# NeoGeo-JAMMA-Supergun_OD.net
KiCad netlist of a schematic drawn in EAGLE
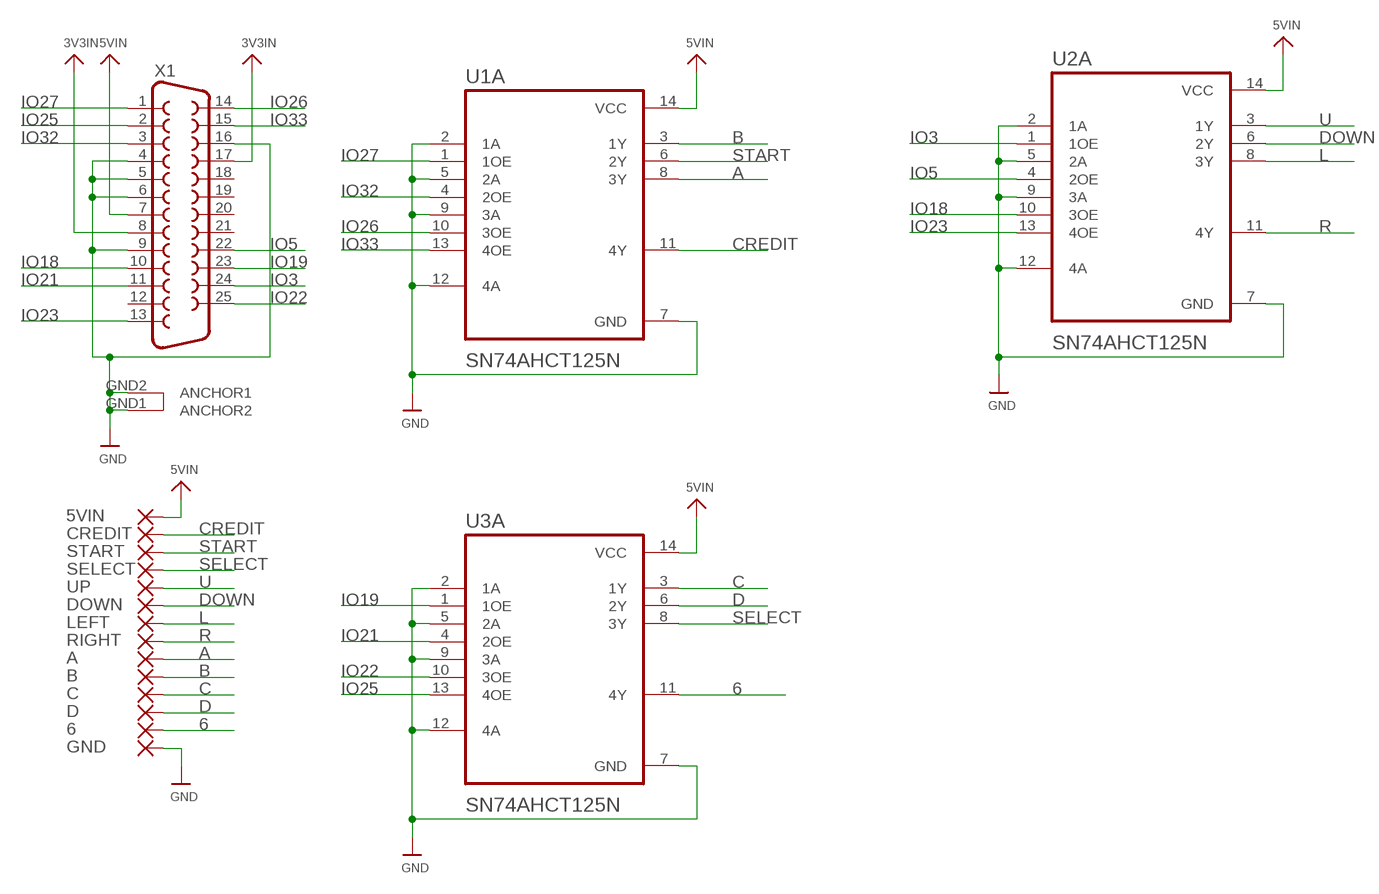
[diagram p0: schematic, sheet 1]

(export (version "E")
  (design (tool "Eeschema 10.0.6"))
  (components
    (comp (ref "5VIN")
      (value "SMD5")
      (footprint "eagle-import:SMD2,54-5,08")
      (libsource (lib "eagle-import") (part "SMD5"))
    )
    (comp (ref "6")
      (value "SMD5")
      (footprint "eagle-import:SMD2,54-5,08")
      (libsource (lib "eagle-import") (part "SMD5"))
    )
    (comp (ref "A")
      (value "SMD5")
      (footprint "eagle-import:SMD2,54-5,08")
      (libsource (lib "eagle-import") (part "SMD5"))
    )
    (comp (ref "B")
      (value "SMD5")
      (footprint "eagle-import:SMD2,54-5,08")
      (libsource (lib "eagle-import") (part "SMD5"))
    )
    (comp (ref "C")
      (value "SMD5")
      (footprint "eagle-import:SMD2,54-5,08")
      (libsource (lib "eagle-import") (part "SMD5"))
    )
    (comp (ref "CREDIT")
      (value "SMD5")
      (footprint "eagle-import:SMD2,54-5,08")
      (libsource (lib "eagle-import") (part "SMD5"))
    )
    (comp (ref "D")
      (value "SMD5")
      (footprint "eagle-import:SMD2,54-5,08")
      (libsource (lib "eagle-import") (part "SMD5"))
    )
    (comp (ref "DOWN")
      (value "SMD5")
      (footprint "eagle-import:SMD2,54-5,08")
      (libsource (lib "eagle-import") (part "SMD5"))
    )
    (comp (ref "GND")
      (value "SMD5")
      (footprint "eagle-import:SMD2,54-5,08")
      (libsource (lib "eagle-import") (part "SMD5"))
    )
    (comp (ref "LEFT")
      (value "SMD5")
      (footprint "eagle-import:SMD2,54-5,08")
      (libsource (lib "eagle-import") (part "SMD5"))
    )
    (comp (ref "RIGHT")
      (value "SMD5")
      (footprint "eagle-import:SMD2,54-5,08")
      (libsource (lib "eagle-import") (part "SMD5"))
    )
    (comp (ref "SELECT")
      (value "SMD5")
      (footprint "eagle-import:SMD2,54-5,08")
      (libsource (lib "eagle-import") (part "SMD5"))
    )
    (comp (ref "START")
      (value "SMD5")
      (footprint "eagle-import:SMD2,54-5,08")
      (libsource (lib "eagle-import") (part "SMD5"))
    )
    (comp (ref "U1A")
      (value "SN74AHCT125N")
      (footprint "eagle-import:DIP794W45P254L1969H508Q14")
      (fields (field (name "MF") "Texas Instruments"))
      (libsource (lib "eagle-import") (part "SN74AHCT125N"))
    )
    (comp (ref "U2A")
      (value "SN74AHCT125N")
      (footprint "eagle-import:DIP794W45P254L1969H508Q14")
      (fields (field (name "MF") "Texas Instruments"))
      (libsource (lib "eagle-import") (part "SN74AHCT125N"))
    )
    (comp (ref "U3A")
      (value "SN74AHCT125N")
      (footprint "eagle-import:DIP794W45P254L1969H508Q14")
      (fields (field (name "MF") "Texas Instruments"))
      (libsource (lib "eagle-import") (part "SN74AHCT125N"))
    )
    (comp (ref "UP")
      (value "SMD5")
      (footprint "eagle-import:SMD2,54-5,08")
      (libsource (lib "eagle-import") (part "SMD5"))
    )
    (comp (ref "X1")
      (value "DB25_FEMALEHP")
      (footprint "eagle-import:F25HP")
      (libsource (lib "eagle-import") (part "DB25_FEMALEHP"))
    )
  )
  (nets
    (net (code "1") (name "/6") (class "Default")
      (node (ref "6") (pin "1") (pinfunction "P_1") (pintype "passive"))
      (node (ref "U3A") (pin "11") (pinfunction "4Y_11") (pintype "output"))
    )
    (net (code "2") (name "/A") (class "Default")
      (node (ref "A") (pin "1") (pinfunction "P_1") (pintype "passive"))
      (node (ref "U1A") (pin "8") (pinfunction "3Y_8") (pintype "output"))
    )
    (net (code "3") (name "/B") (class "Default")
      (node (ref "B") (pin "1") (pinfunction "P_1") (pintype "passive"))
      (node (ref "U1A") (pin "3") (pinfunction "1Y_3") (pintype "output"))
    )
    (net (code "4") (name "/C") (class "Default")
      (node (ref "C") (pin "1") (pinfunction "P_1") (pintype "passive"))
      (node (ref "U3A") (pin "3") (pinfunction "1Y_3") (pintype "output"))
    )
    (net (code "5") (name "/CREDIT") (class "Default")
      (node (ref "CREDIT") (pin "1") (pinfunction "P_1") (pintype "passive"))
      (node (ref "U1A") (pin "11") (pinfunction "4Y_11") (pintype "output"))
    )
    (net (code "6") (name "/D") (class "Default")
      (node (ref "D") (pin "1") (pinfunction "P_1") (pintype "passive"))
      (node (ref "U3A") (pin "6") (pinfunction "2Y_6") (pintype "output"))
    )
    (net (code "7") (name "/DOWN") (class "Default")
      (node (ref "DOWN") (pin "1") (pinfunction "P_1") (pintype "passive"))
      (node (ref "U2A") (pin "6") (pinfunction "2Y_6") (pintype "output"))
    )
    (net (code "8") (name "/IO3") (class "Default")
      (node (ref "U2A") (pin "1") (pinfunction "1OE_1") (pintype "input"))
      (node (ref "X1") (pin "24") (pinfunction "24_24") (pintype "passive"))
    )
    (net (code "9") (name "/IO5") (class "Default")
      (node (ref "U2A") (pin "4") (pinfunction "2OE_4") (pintype "input"))
      (node (ref "X1") (pin "22") (pinfunction "22_22") (pintype "passive"))
    )
    (net (code "10") (name "/IO18") (class "Default")
      (node (ref "U2A") (pin "10") (pinfunction "3OE_10") (pintype "input"))
      (node (ref "X1") (pin "10") (pinfunction "10_10") (pintype "passive"))
    )
    (net (code "11") (name "/IO19") (class "Default")
      (node (ref "U3A") (pin "1") (pinfunction "1OE_1") (pintype "input"))
      (node (ref "X1") (pin "23") (pinfunction "23_23") (pintype "passive"))
    )
    (net (code "12") (name "/IO21") (class "Default")
      (node (ref "U3A") (pin "4") (pinfunction "2OE_4") (pintype "input"))
      (node (ref "X1") (pin "11") (pinfunction "11_11") (pintype "passive"))
    )
    (net (code "13") (name "/IO22") (class "Default")
      (node (ref "U3A") (pin "10") (pinfunction "3OE_10") (pintype "input"))
      (node (ref "X1") (pin "25") (pinfunction "25_25") (pintype "passive"))
    )
    (net (code "14") (name "/IO23") (class "Default")
      (node (ref "U2A") (pin "13") (pinfunction "4OE_13") (pintype "input"))
      (node (ref "X1") (pin "13") (pinfunction "13_13") (pintype "passive"))
    )
    (net (code "15") (name "/IO25") (class "Default")
      (node (ref "U3A") (pin "13") (pinfunction "4OE_13") (pintype "input"))
      (node (ref "X1") (pin "2") (pinfunction "2_2") (pintype "passive"))
    )
    (net (code "16") (name "/IO26") (class "Default")
      (node (ref "U1A") (pin "10") (pinfunction "3OE_10") (pintype "input"))
      (node (ref "X1") (pin "14") (pinfunction "14_14") (pintype "passive"))
    )
    (net (code "17") (name "/IO27") (class "Default")
      (node (ref "U1A") (pin "1") (pinfunction "1OE_1") (pintype "input"))
      (node (ref "X1") (pin "1") (pinfunction "1_1") (pintype "passive"))
    )
    (net (code "18") (name "/IO32") (class "Default")
      (node (ref "U1A") (pin "4") (pinfunction "2OE_4") (pintype "input"))
      (node (ref "X1") (pin "3") (pinfunction "3_3") (pintype "passive"))
    )
    (net (code "19") (name "/IO33") (class "Default")
      (node (ref "U1A") (pin "13") (pinfunction "4OE_13") (pintype "input"))
      (node (ref "X1") (pin "15") (pinfunction "15_15") (pintype "passive"))
    )
    (net (code "20") (name "/L") (class "Default")
      (node (ref "LEFT") (pin "1") (pinfunction "P_1") (pintype "passive"))
      (node (ref "U2A") (pin "8") (pinfunction "3Y_8") (pintype "output"))
    )
    (net (code "21") (name "/R") (class "Default")
      (node (ref "RIGHT") (pin "1") (pinfunction "P_1") (pintype "passive"))
      (node (ref "U2A") (pin "11") (pinfunction "4Y_11") (pintype "output"))
    )
    (net (code "22") (name "/SELECT") (class "Default")
      (node (ref "SELECT") (pin "1") (pinfunction "P_1") (pintype "passive"))
      (node (ref "U3A") (pin "8") (pinfunction "3Y_8") (pintype "output"))
    )
    (net (code "23") (name "/START") (class "Default")
      (node (ref "START") (pin "1") (pinfunction "P_1") (pintype "passive"))
      (node (ref "U1A") (pin "6") (pinfunction "2Y_6") (pintype "output"))
    )
    (net (code "24") (name "/U") (class "Default")
      (node (ref "U2A") (pin "3") (pinfunction "1Y_3") (pintype "output"))
      (node (ref "UP") (pin "1") (pinfunction "P_1") (pintype "passive"))
    )
    (net (code "25") (name "3V3IN") (class "Default")
      (node (ref "X1") (pin "17") (pinfunction "17_17") (pintype "passive"))
      (node (ref "X1") (pin "8") (pinfunction "8_8") (pintype "passive"))
    )
    (net (code "26") (name "5VIN") (class "Default")
      (node (ref "5VIN") (pin "1") (pinfunction "P_1") (pintype "passive"))
      (node (ref "U1A") (pin "14") (pinfunction "VCC_14") (pintype "power_in"))
      (node (ref "U2A") (pin "14") (pinfunction "VCC_14") (pintype "power_in"))
      (node (ref "U3A") (pin "14") (pinfunction "VCC_14") (pintype "power_in"))
      (node (ref "X1") (pin "7") (pinfunction "7_7") (pintype "passive"))
    )
    (net (code "27") (name "GND") (class "Default")
      (node (ref "GND") (pin "1") (pinfunction "P_1") (pintype "passive"))
      (node (ref "U1A") (pin "12") (pinfunction "4A_12") (pintype "bidirectional"))
      (node (ref "U1A") (pin "2") (pinfunction "1A_2") (pintype "input"))
      (node (ref "U1A") (pin "5") (pinfunction "2A_5") (pintype "input"))
      (node (ref "U1A") (pin "7") (pinfunction "GND_7") (pintype "power_in"))
      (node (ref "U1A") (pin "9") (pinfunction "3A_9") (pintype "input"))
      (node (ref "U2A") (pin "12") (pinfunction "4A_12") (pintype "bidirectional"))
      (node (ref "U2A") (pin "2") (pinfunction "1A_2") (pintype "input"))
      (node (ref "U2A") (pin "5") (pinfunction "2A_5") (pintype "input"))
      (node (ref "U2A") (pin "7") (pinfunction "GND_7") (pintype "power_in"))
      (node (ref "U2A") (pin "9") (pinfunction "3A_9") (pintype "input"))
      (node (ref "U3A") (pin "12") (pinfunction "4A_12") (pintype "bidirectional"))
      (node (ref "U3A") (pin "2") (pinfunction "1A_2") (pintype "input"))
      (node (ref "U3A") (pin "5") (pinfunction "2A_5") (pintype "input"))
      (node (ref "U3A") (pin "7") (pinfunction "GND_7") (pintype "power_in"))
      (node (ref "U3A") (pin "9") (pinfunction "3A_9") (pintype "input"))
      (node (ref "X1") (pin "16") (pinfunction "16_16") (pintype "passive"))
      (node (ref "X1") (pin "4") (pinfunction "4_4") (pintype "passive"))
      (node (ref "X1") (pin "5") (pinfunction "5_5") (pintype "passive"))
      (node (ref "X1") (pin "6") (pinfunction "6_6") (pintype "passive"))
      (node (ref "X1") (pin "9") (pinfunction "9_9") (pintype "passive"))
      (node (ref "X1") (pin "GND1") (pinfunction "ANCHOR2_GND1") (pintype "bidirectional"))
      (node (ref "X1") (pin "GND2") (pinfunction "ANCHOR1_GND2") (pintype "bidirectional"))
    )
    (net (code "28") (name "unconnected-(X1-Pad12)") (class "Default")
      (node (ref "X1") (pin "12") (pinfunction "12_12") (pintype "passive"))
    )
    (net (code "29") (name "unconnected-(X1-Pad18)") (class "Default")
      (node (ref "X1") (pin "18") (pinfunction "18_18") (pintype "passive"))
    )
    (net (code "30") (name "unconnected-(X1-Pad19)") (class "Default")
      (node (ref "X1") (pin "19") (pinfunction "19_19") (pintype "passive"))
    )
    (net (code "31") (name "unconnected-(X1-Pad20)") (class "Default")
      (node (ref "X1") (pin "20") (pinfunction "20_20") (pintype "passive"))
    )
    (net (code "32") (name "unconnected-(X1-Pad21)") (class "Default")
      (node (ref "X1") (pin "21") (pinfunction "21_21") (pintype "passive"))
    )
  )
)
